# Power_Distribution_-_Spare_5.net
KiCad netlist of a schematic drawn in Altium Designer
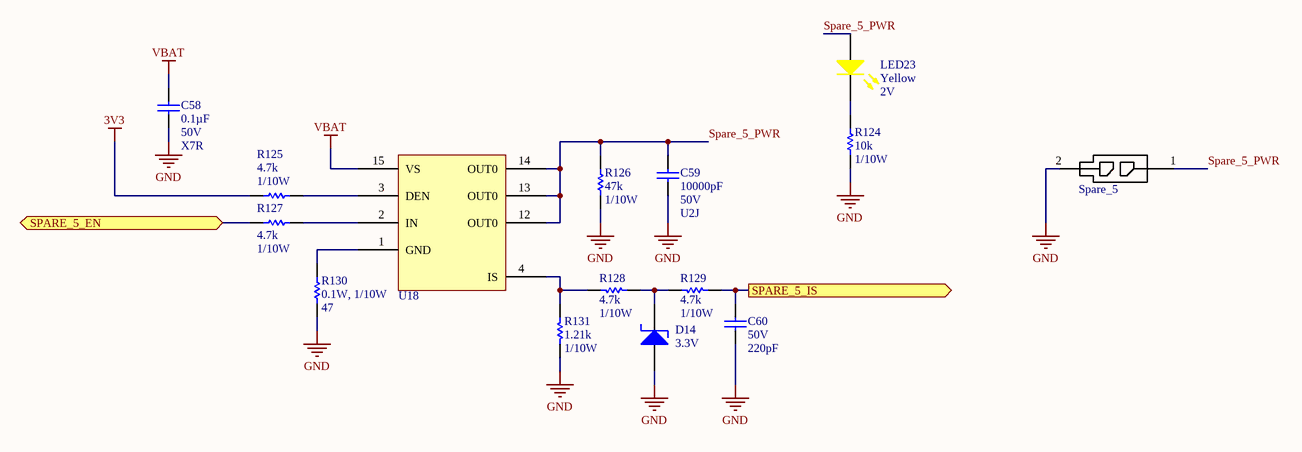
[diagram p0: Power Distribution - Spare 5.SchDoc]

(export (version "E")
  (design (tool "Eeschema 10.0.6"))
  (components
    (comp (ref "C58")
      (value "CAP CER 0.1UF 50V 10% X7R 0603")
      (footprint "CAP, 0603")
      (description "0.10µF ±10% 50V Ceramic Capacitor X7R 0603 (1608 Metric)")
      (fields
        (field (name "TOLERANCE") "±10%")
        (field (name "CAPACITANCE") "0.1µF")
        (field (name "VOLTAGE") "50V")
        (field (name "TEMPERATURE COEFFICIENT") "X7R")
      )
      (libsource (lib "Schematic Diagrams") (part "CAP CER 0.1UF 50V 10% X7R 0603"))
    )
    (comp (ref "C59")
      (value "CAP CER 10nF 50V 5% X7R 0603")
      (footprint "CAP, 0603")
      (description "10000pF ±5% 50V Ceramic Capacitor U2J 0603 (1608 Metric)")
      (fields
        (field (name "TOLERANCE") "±5%")
        (field (name "CAPACITANCE") "10000pF")
        (field (name "VOLTAGE") "50V")
        (field (name "TEMPERATURE COEFFICIENT") "U2J")
      )
      (libsource (lib "Schematic Diagrams") (part "CAP CER 10nF 50V 5% X7R 0603"))
    )
    (comp (ref "C60")
      (value "CAP CER 220PF 50V C0G/NP0 0603")
      (footprint "CAP, 0603")
      (description "220pF ±5% 50V Ceramic Capacitor C0G, NP0 0603 (1608 Metric)")
      (fields
        (field (name "MANUFACTURER") "KEMET")
        (field (name "TOLERANCE") "5%")
        (field (name "VOLTAGE RATING") "50V")
        (field (name "CAPACITANCE") "220pF")
      )
      (libsource (lib "Schematic Diagrams") (part "CAP CER 220PF 50V C0G/NP0 0603"))
    )
    (comp (ref "D14")
      (value "DIODE ZENER 3.3V 200MW SOD323")
      (footprint "sod-323")
      (description "Zener Diode 3.3V 200mW ±5% Surface Mount SOD-323")
      (fields (field (name "VOLTAGE") "3.3V"))
      (libsource (lib "Schematic Diagrams") (part "DIODE ZENER 3.3V 200MW SOD323"))
    )
    (comp (ref "LED23")
      (value "LED YELLOW CLEAR 2.1V 0603")
      (footprint "LED_0603")
      (description "Yellow 590nm LED Indication - Discrete 2V 0603 (1608 Metric)")
      (fields
        (field (name "MANUFACTURER") "Wurth Electronics Inc.")
        (field (name "MANUFACTURER PART NUMBER") "150060YS75000")
        (field (name "COLOR") "Yellow")
        (field (name "VOLTAGE - FORWARD (VF) (TYP)") "2V")
      )
      (libsource (lib "Schematic Diagrams") (part "LED YELLOW CLEAR 2.1V 0603"))
    )
    (comp (ref "R124")
      (value "RES 10K OHM 1% 1/10W 0603")
      (footprint "RES, 0603")
      (description "RES SMD 10K OHM 1% 1/10W 0603")
      (fields
        (field (name "TOLERANCE") "±1%")
        (field (name "RESISTANCE") "10k")
        (field (name "POWER") "1/10W")
      )
      (libsource (lib "Schematic Diagrams") (part "RES 10K OHM 1% 1/10W 0603"))
    )
    (comp (ref "R125")
      (value "RES 4.7K OHM 1% 1/10W 0603")
      (footprint "RES, 0603")
      (description "4.7k Ohm ±1% 0.1W, 1/10W Chip Resistor 0603 (1608 Metric) Moisture Resistant Thick Film")
      (fields
        (field (name "TOLERANCE") "±1%")
        (field (name "RESISTANCE (OHMS)") "4.7k")
        (field (name "POWER (WATTS)") "1/10W")
      )
      (libsource (lib "Schematic Diagrams") (part "RES 4.7K OHM 1% 1/10W 0603"))
    )
    (comp (ref "R126")
      (value "RES 47K OHM 1% 1/10W 0603")
      (footprint "RES, 0603")
      (description "47 kOhms ±1% 0.1W, 1/10W Chip Resistor 0603 (1608 Metric) Automotive AEC-Q200 Thick Film")
      (fields
        (field (name "MANUFACTURER") "Panasonic")
        (field (name "MANUFACTURER PART NUMBER") "ERJ3EKF4702V")
        (field (name "RESISTANCE") "47k")
        (field (name "POWER RATING") "1/10W")
      )
      (libsource (lib "Schematic Diagrams") (part "RES 47K OHM 1% 1/10W 0603"))
    )
    (comp (ref "R127")
      (value "RES 4.7K OHM 1% 1/10W 0603")
      (footprint "RES, 0603")
      (description "4.7k Ohm ±1% 0.1W, 1/10W Chip Resistor 0603 (1608 Metric) Moisture Resistant Thick Film")
      (fields
        (field (name "TOLERANCE") "±1%")
        (field (name "RESISTANCE (OHMS)") "4.7k")
        (field (name "POWER (WATTS)") "1/10W")
      )
      (libsource (lib "Schematic Diagrams") (part "RES 4.7K OHM 1% 1/10W 0603"))
    )
    (comp (ref "R128")
      (value "RES 4.7K OHM 1% 1/10W 0603")
      (footprint "RES, 0603")
      (description "4.7k Ohm ±1% 0.1W, 1/10W Chip Resistor 0603 (1608 Metric) Moisture Resistant Thick Film")
      (fields
        (field (name "TOLERANCE") "±1%")
        (field (name "RESISTANCE (OHMS)") "4.7k")
        (field (name "POWER (WATTS)") "1/10W")
      )
      (libsource (lib "Schematic Diagrams") (part "RES 4.7K OHM 1% 1/10W 0603"))
    )
    (comp (ref "R129")
      (value "RES 4.7K OHM 1% 1/10W 0603")
      (footprint "RES, 0603")
      (description "4.7k Ohm ±1% 0.1W, 1/10W Chip Resistor 0603 (1608 Metric) Moisture Resistant Thick Film")
      (fields
        (field (name "TOLERANCE") "±1%")
        (field (name "RESISTANCE (OHMS)") "4.7k")
        (field (name "POWER (WATTS)") "1/10W")
      )
      (libsource (lib "Schematic Diagrams") (part "RES 4.7K OHM 1% 1/10W 0603"))
    )
    (comp (ref "R130")
      (value "RES SMD 47 OHM 1% 1/10W 0603")
      (footprint "RES, 0603")
      (fields
        (field (name "TOLERANCE") "±1%")
        (field (name "POWER (WATTS)") "0.1W, 1/10W")
        (field (name "VALUES") "47")
      )
      (libsource (lib "Schematic Diagrams") (part "RES SMD 47 OHM 1% 1/10W 0603"))
    )
    (comp (ref "R131")
      (value "RES 1.21K OHM 1% 1/10W 0603")
      (footprint "RES, 0603")
      (description "1.21k Ohm ±1% 0.1W, 1/10W Chip Resistor 0603 (1608 Metric) Moisture Resistant Thick Film")
      (fields
        (field (name "TOLERANCE") "±1%")
        (field (name "RESISTANCE") "1.21k")
        (field (name "POWER") "1/10W")
      )
      (libsource (lib "Schematic Diagrams") (part "RES 1.21K OHM 1% 1/10W 0603"))
    )
    (comp (ref "Spare_5")
      (value "CONN 2POS MICRO-FIT 3mm")
      (footprint "CONN, 2POS MICRO-FIT")
      (description "Connector Header Through Hole 2 position")
      (fields (field (name "MANUFACTURER") "Molex") (field (name "MANUFACTURER PART NUMBER") "43045-0227"))
      (libsource (lib "Schematic Diagrams") (part "CONN 2POS MICRO-FIT 3mm"))
    )
    (comp (ref "U18")
      (value "IC LOAD SWITCH BTS70401EPA PG-TSDSO-14-22")
      (footprint "IC LOAD SWITCH PG-TSDSO-14-22")
      (description "Power Switch/Driver 1:1 N-Channel 4.5A PG-TSDSO-14-22")
      (fields
        (field (name "MANUFACTURER") "Infineon")
        (field (name "MANUFACTURER PART NUMBER") "BTS70401EPAXUMA1")
      )
      (libsource (lib "Schematic Diagrams") (part "IC LOAD SWITCH BTS70401EPA PG-TSDSO-14-22"))
    )
  )
  (nets
    (net (code "1") (name "/SPARE_5_EN") (class "Default")
      (node (ref "R127") (pin "1") (pinfunction "1_1") (pintype "passive"))
    )
    (net (code "2") (name "/SPARE_5_IS") (class "Default")
      (node (ref "C60") (pin "1") (pinfunction "1_1") (pintype "passive"))
      (node (ref "R129") (pin "1") (pinfunction "1_1") (pintype "passive"))
    )
    (net (code "3") (name "/Spare_5_PWR") (class "Default")
      (node (ref "C59") (pin "1") (pinfunction "1_1") (pintype "passive"))
      (node (ref "LED23") (pin "1") (pinfunction "A_1") (pintype "passive"))
      (node (ref "R126") (pin "1") (pinfunction "1_1") (pintype "passive"))
      (node (ref "Spare_5") (pin "1") (pinfunction "1_1") (pintype "passive"))
      (node (ref "U18") (pin "12") (pinfunction "OUT0_12") (pintype "passive"))
      (node (ref "U18") (pin "13") (pinfunction "OUT0_13") (pintype "passive"))
      (node (ref "U18") (pin "14") (pinfunction "OUT0_14") (pintype "passive"))
    )
    (net (code "4") (name "3V3") (class "Default")
      (node (ref "R125") (pin "1") (pinfunction "1_1") (pintype "passive"))
    )
    (net (code "5") (name "GND") (class "Default")
      (node (ref "C58") (pin "2") (pinfunction "2_2") (pintype "passive"))
      (node (ref "C59") (pin "2") (pinfunction "2_2") (pintype "passive"))
      (node (ref "C60") (pin "2") (pinfunction "2_2") (pintype "passive"))
      (node (ref "D14") (pin "1") (pinfunction "A_1") (pintype "passive"))
      (node (ref "R124") (pin "2") (pinfunction "2_2") (pintype "passive"))
      (node (ref "R126") (pin "2") (pinfunction "2_2") (pintype "passive"))
      (node (ref "R130") (pin "2") (pinfunction "2_2") (pintype "passive"))
      (node (ref "R131") (pin "2") (pinfunction "2_2") (pintype "passive"))
      (node (ref "Spare_5") (pin "2") (pinfunction "2_2") (pintype "passive"))
    )
    (net (code "6") (name "Net-(D14-K)") (class "Default")
      (node (ref "D14") (pin "2") (pinfunction "K_2") (pintype "passive"))
      (node (ref "R128") (pin "1") (pinfunction "1_1") (pintype "passive"))
      (node (ref "R129") (pin "2") (pinfunction "2_2") (pintype "passive"))
    )
    (net (code "7") (name "Net-(LED23-K)") (class "Default")
      (node (ref "LED23") (pin "2") (pinfunction "K_2") (pintype "passive"))
      (node (ref "R124") (pin "1") (pinfunction "1_1") (pintype "passive"))
    )
    (net (code "8") (name "Net-(U18-DEN)") (class "Default")
      (node (ref "R125") (pin "2") (pinfunction "2_2") (pintype "passive"))
      (node (ref "U18") (pin "3") (pinfunction "DEN_3") (pintype "passive"))
    )
    (net (code "9") (name "Net-(U18-GND)") (class "Default")
      (node (ref "R130") (pin "1") (pinfunction "1_1") (pintype "passive"))
      (node (ref "U18") (pin "1") (pinfunction "GND_1") (pintype "passive"))
    )
    (net (code "10") (name "Net-(U18-IN)") (class "Default")
      (node (ref "R127") (pin "2") (pinfunction "2_2") (pintype "passive"))
      (node (ref "U18") (pin "2") (pinfunction "IN_2") (pintype "passive"))
    )
    (net (code "11") (name "Net-(U18-IS)") (class "Default")
      (node (ref "R128") (pin "2") (pinfunction "2_2") (pintype "passive"))
      (node (ref "R131") (pin "1") (pinfunction "1_1") (pintype "passive"))
      (node (ref "U18") (pin "4") (pinfunction "IS_4") (pintype "passive"))
    )
    (net (code "12") (name "VBAT") (class "Default")
      (node (ref "C58") (pin "1") (pinfunction "1_1") (pintype "passive"))
      (node (ref "U18") (pin "15") (pinfunction "VS_15") (pintype "passive"))
    )
  )
)
